# MCU.net
KiCad netlist of a schematic drawn in Altium Designer
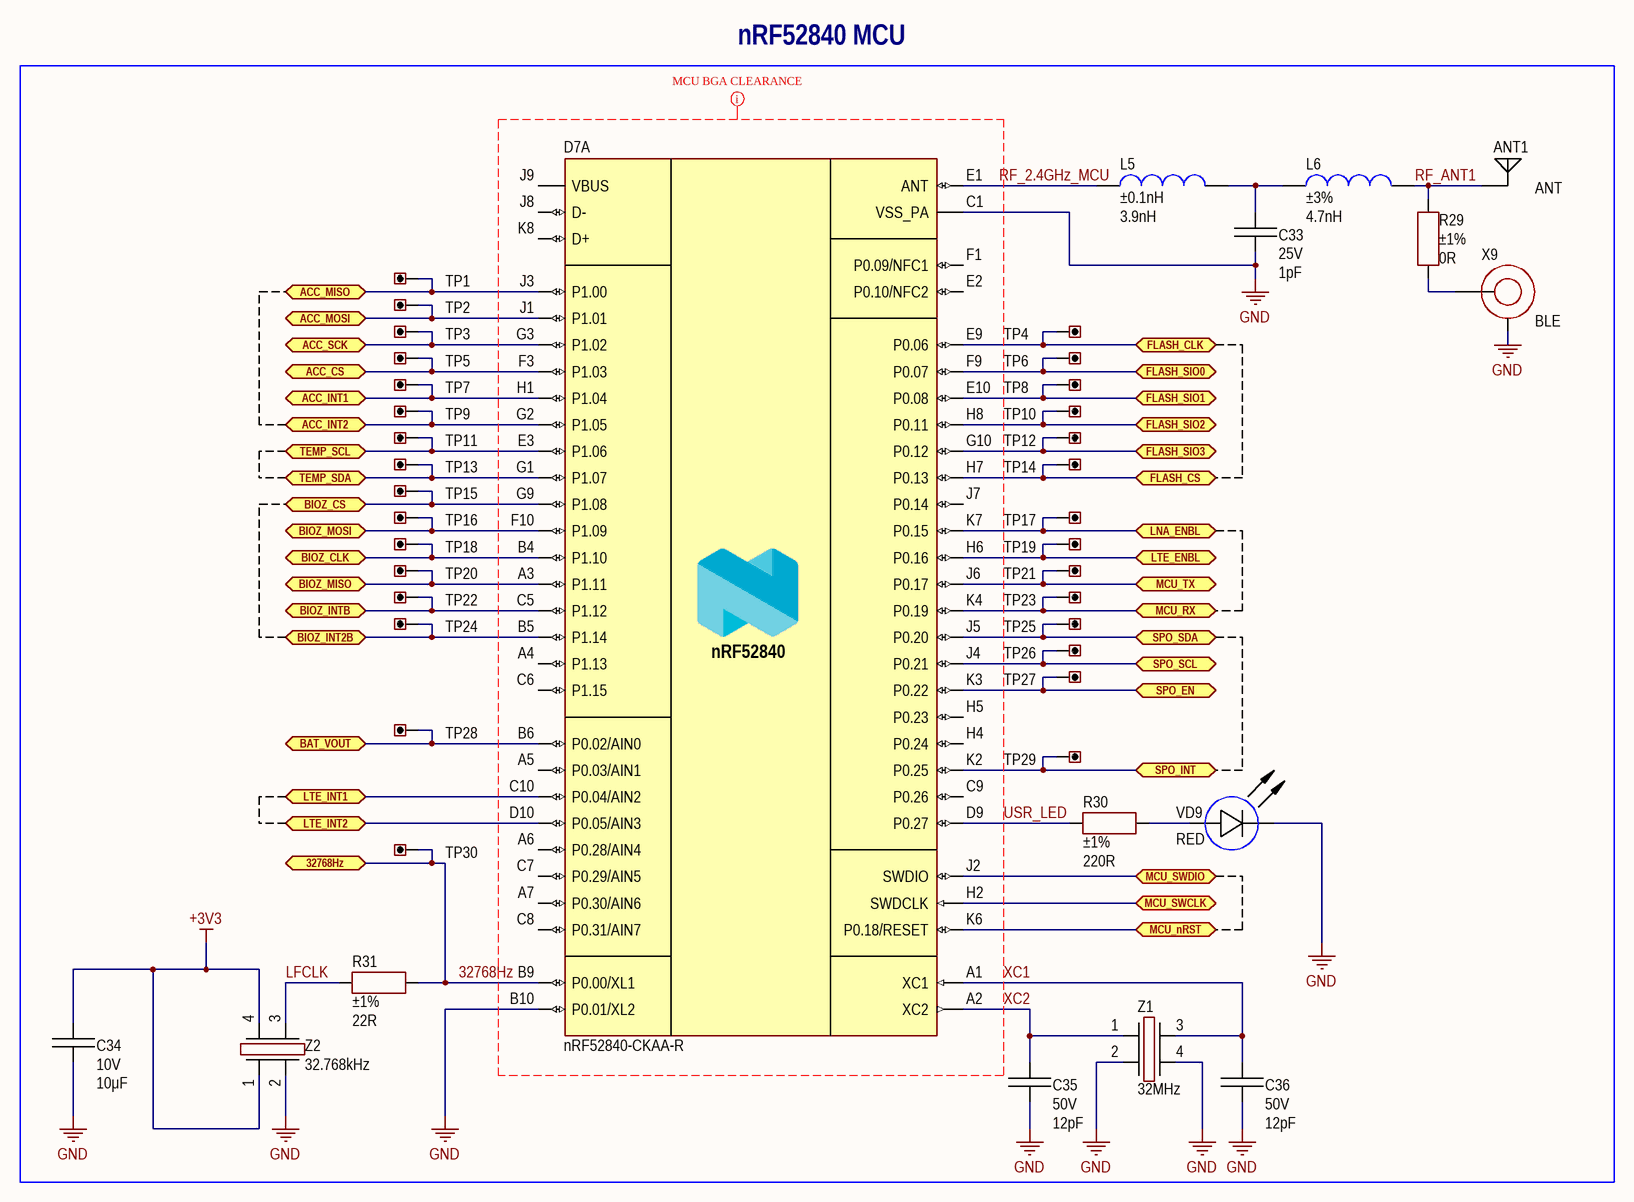
[diagram p0: MCU.SchDoc]

(export (version "E")
  (design (tool "Eeschema 10.0.6"))
  (components
    (comp (ref "ANT1")
      (value "~")
      (footprint "ANT: ANT2012LL00R2400A")
      (description "2.45GHz Bluetooth, ISM, Wi-Fi, Zigbee Chip RF Antenna 2.4GHz ~ 2.5GHz 3.77dBi Solder Surface Mount")
      (fields
        (field (name "MANUFACTURER") "Yageo")
        (field (name "VALUEMANUFACTURERPARTNUMBER") "Ceramic antenna, 2x1.25mm")
        (field (name "COMMENTTEXT") "ANT")
      )
      (libsource (lib "MyLib") (part "ANT2012LL00R2400A"))
    )
    (comp (ref "C33")
      (value "1pF")
      (footprint "CAP: 0201")
      (description "1 pF ±0.05pF 25V Ceramic Capacitor C0G, NP0 0201 (0603 Metric)")
      (fields
        (field (name "MANUFACTURER") "Murata Electronics")
        (field (name "PARTNUMBER") "GJM0335C1E1R0WB01D")
        (field (name "VOLTAGE") "25V")
      )
      (libsource (lib "capacitor") (part "Ceramic_0201"))
    )
    (comp (ref "C34")
      (value "10μF")
      (footprint "CAP: 0805")
      (description "10 µF ±10% 10V Ceramic Capacitor X7R 0805 (2012 Metric)")
      (fields
        (field (name "MANUFACTURER") "Yageo")
        (field (name "PARTNUMBER") "CC0805KFX7R6BB106")
        (field (name "VOLTAGE") "10V")
      )
      (libsource (lib "capacitor") (part "Ceramic_0805"))
    )
    (comp (ref "C35")
      (value "12pF")
      (footprint "CAP: 0805")
      (description "12 pF ±1% 50V Ceramic Capacitor C0G, NP0 0805 (2012 Metric)")
      (fields
        (field (name "MANUFACTURER") "Yageo")
        (field (name "PARTNUMBER") "CC0805FRNPO9BN120")
        (field (name "VOLTAGE") "50V")
      )
      (libsource (lib "capacitor") (part "Ceramic_0805"))
    )
    (comp (ref "C36")
      (value "12pF")
      (footprint "CAP: 0805")
      (description "12 pF ±1% 50V Ceramic Capacitor C0G, NP0 0805 (2012 Metric)")
      (fields
        (field (name "MANUFACTURER") "Yageo")
        (field (name "PARTNUMBER") "CC0805FRNPO9BN120")
        (field (name "VOLTAGE") "50V")
      )
      (libsource (lib "capacitor") (part "Ceramic_0805"))
    )
    (comp (ref "D7")
      (value "~")
      (footprint "MCU: nRF52840_WLCP93")
      (description "MCU")
      (fields
        (field (name "MANUFACTURER") "Nordic Semiconductor")
        (field (name "VALUEMANUFACTURERPARTNUMBER") "IC microcontroller, 32bit, Cortex-M4, 64 MHz, 1 MB, 256 kB, , , 93-WLCSP")
        (field (name "PARTNUMBER") "nRF52840-CKAA-R")
      )
      (libsource (lib "MyLib") (part "nRF52840"))
    )
    (comp (ref "L5")
      (value "3.9nH")
      (footprint "IND: 0201")
      (description "3.9 nH Unshielded Thick Film Inductor 400 mA 300mOhm Max 0201 (0603 Metric)")
      (fields
        (field (name "MANUFACTURER") "Murata Electronics")
        (field (name "PARTNUMBER") "LQP03TN3N9B02D")
        (field (name "TOLERANCE") "±0.1nH")
      )
      (libsource (lib "inductor") (part "Inductor_0201"))
    )
    (comp (ref "L6")
      (value "4.7nH")
      (footprint "IND: 0201")
      (description "4.7 nH Unshielded Thick Film Inductor 350 mA 400mOhm Max 0201 (0603 Metric)")
      (fields
        (field (name "MANUFACTURER") "Murata Electronics")
        (field (name "PARTNUMBER") "LQP03TN4N7H02D")
        (field (name "TOLERANCE") "±3%")
      )
      (libsource (lib "inductor") (part "Inductor_0201"))
    )
    (comp (ref "R29")
      (value "0R")
      (footprint "RES: 0201")
      (description "0 Ohms Jumper 0.05W, 1/20W Chip Resistor 0201 (0603 Metric) Moisture Resistant Thick Film")
      (fields
        (field (name "MANUFACTURER") "Yageo")
        (field (name "PARTNUMBER") "RC0201FR-070RL")
        (field (name "TOLERANCE") "±1%")
      )
      (libsource (lib "resistor") (part "Resistor_0201"))
    )
    (comp (ref "R30")
      (value "220R")
      (footprint "RES: 0805")
      (description "22 Ohms ±1% 0.125W, 1/8W Chip Resistor 0805 (2012 Metric) Moisture Resistant Thick Film")
      (fields
        (field (name "MANUFACTURER") "Yageo")
        (field (name "PARTNUMBER") "RC0805JR-07220RL")
        (field (name "TOLERANCE") "±1%")
      )
      (libsource (lib "resistor") (part "Resistor_0805"))
    )
    (comp (ref "R31")
      (value "22R")
      (footprint "RES: 0805")
      (description "22 Ohms ±1% 0.125W, 1/8W Chip Resistor 0805 (2012 Metric) Moisture Resistant Thick Film")
      (fields
        (field (name "MANUFACTURER") "Yageo")
        (field (name "PARTNUMBER") "RC0805FR-0722RL")
        (field (name "TOLERANCE") "±1%")
      )
      (libsource (lib "resistor") (part "Resistor_0805"))
    )
    (comp (ref "TP1")
      (value "~")
      (footprint "CON: 5000 (Keystone)")
      (fields
        (field (name "MANUFACTURER") "Keystone")
        (field (name "VALUEMANUFACTURERPARTNUMBER") "Test point, Keystone, 5000")
        (field (name "PARTNUMBER") "5000")
      )
      (libsource (lib "connector") (part "Connector_Test_Point"))
    )
    (comp (ref "TP2")
      (value "~")
      (footprint "CON: 5000 (Keystone)")
      (fields
        (field (name "MANUFACTURER") "Keystone")
        (field (name "VALUEMANUFACTURERPARTNUMBER") "Test point, Keystone, 5000")
        (field (name "PARTNUMBER") "5000")
      )
      (libsource (lib "connector") (part "Connector_Test_Point"))
    )
    (comp (ref "TP3")
      (value "~")
      (footprint "CON: 5000 (Keystone)")
      (fields
        (field (name "MANUFACTURER") "Keystone")
        (field (name "VALUEMANUFACTURERPARTNUMBER") "Test point, Keystone, 5000")
        (field (name "PARTNUMBER") "5000")
      )
      (libsource (lib "connector") (part "Connector_Test_Point"))
    )
    (comp (ref "TP4")
      (value "~")
      (footprint "CON: 5000 (Keystone)")
      (fields
        (field (name "MANUFACTURER") "Keystone")
        (field (name "VALUEMANUFACTURERPARTNUMBER") "Test point, Keystone, 5000")
        (field (name "PARTNUMBER") "5000")
      )
      (libsource (lib "") (part "Connector_Test_Point_1"))
    )
    (comp (ref "TP5")
      (value "~")
      (footprint "CON: 5000 (Keystone)")
      (fields
        (field (name "MANUFACTURER") "Keystone")
        (field (name "VALUEMANUFACTURERPARTNUMBER") "Test point, Keystone, 5000")
        (field (name "PARTNUMBER") "5000")
      )
      (libsource (lib "connector") (part "Connector_Test_Point"))
    )
    (comp (ref "TP6")
      (value "~")
      (footprint "CON: 5000 (Keystone)")
      (fields
        (field (name "MANUFACTURER") "Keystone")
        (field (name "VALUEMANUFACTURERPARTNUMBER") "Test point, Keystone, 5000")
        (field (name "PARTNUMBER") "5000")
      )
      (libsource (lib "") (part "Connector_Test_Point_1"))
    )
    (comp (ref "TP7")
      (value "~")
      (footprint "CON: 5000 (Keystone)")
      (fields
        (field (name "MANUFACTURER") "Keystone")
        (field (name "VALUEMANUFACTURERPARTNUMBER") "Test point, Keystone, 5000")
        (field (name "PARTNUMBER") "5000")
      )
      (libsource (lib "connector") (part "Connector_Test_Point"))
    )
    (comp (ref "TP8")
      (value "~")
      (footprint "CON: 5000 (Keystone)")
      (fields
        (field (name "MANUFACTURER") "Keystone")
        (field (name "VALUEMANUFACTURERPARTNUMBER") "Test point, Keystone, 5000")
        (field (name "PARTNUMBER") "5000")
      )
      (libsource (lib "") (part "Connector_Test_Point_1"))
    )
    (comp (ref "TP9")
      (value "~")
      (footprint "CON: 5000 (Keystone)")
      (fields
        (field (name "MANUFACTURER") "Keystone")
        (field (name "VALUEMANUFACTURERPARTNUMBER") "Test point, Keystone, 5000")
        (field (name "PARTNUMBER") "5000")
      )
      (libsource (lib "connector") (part "Connector_Test_Point"))
    )
    (comp (ref "TP10")
      (value "~")
      (footprint "CON: 5000 (Keystone)")
      (fields
        (field (name "MANUFACTURER") "Keystone")
        (field (name "VALUEMANUFACTURERPARTNUMBER") "Test point, Keystone, 5000")
        (field (name "PARTNUMBER") "5000")
      )
      (libsource (lib "") (part "Connector_Test_Point_1"))
    )
    (comp (ref "TP11")
      (value "~")
      (footprint "CON: 5000 (Keystone)")
      (fields
        (field (name "MANUFACTURER") "Keystone")
        (field (name "VALUEMANUFACTURERPARTNUMBER") "Test point, Keystone, 5000")
        (field (name "PARTNUMBER") "5000")
      )
      (libsource (lib "connector") (part "Connector_Test_Point"))
    )
    (comp (ref "TP12")
      (value "~")
      (footprint "CON: 5000 (Keystone)")
      (fields
        (field (name "MANUFACTURER") "Keystone")
        (field (name "VALUEMANUFACTURERPARTNUMBER") "Test point, Keystone, 5000")
        (field (name "PARTNUMBER") "5000")
      )
      (libsource (lib "") (part "Connector_Test_Point_1"))
    )
    (comp (ref "TP13")
      (value "~")
      (footprint "CON: 5000 (Keystone)")
      (fields
        (field (name "MANUFACTURER") "Keystone")
        (field (name "VALUEMANUFACTURERPARTNUMBER") "Test point, Keystone, 5000")
        (field (name "PARTNUMBER") "5000")
      )
      (libsource (lib "connector") (part "Connector_Test_Point"))
    )
    (comp (ref "TP14")
      (value "~")
      (footprint "CON: 5000 (Keystone)")
      (fields
        (field (name "MANUFACTURER") "Keystone")
        (field (name "VALUEMANUFACTURERPARTNUMBER") "Test point, Keystone, 5000")
        (field (name "PARTNUMBER") "5000")
      )
      (libsource (lib "") (part "Connector_Test_Point_1"))
    )
    (comp (ref "TP15")
      (value "~")
      (footprint "CON: 5000 (Keystone)")
      (fields
        (field (name "MANUFACTURER") "Keystone")
        (field (name "VALUEMANUFACTURERPARTNUMBER") "Test point, Keystone, 5000")
        (field (name "PARTNUMBER") "5000")
      )
      (libsource (lib "connector") (part "Connector_Test_Point"))
    )
    (comp (ref "TP16")
      (value "~")
      (footprint "CON: 5000 (Keystone)")
      (fields
        (field (name "MANUFACTURER") "Keystone")
        (field (name "VALUEMANUFACTURERPARTNUMBER") "Test point, Keystone, 5000")
        (field (name "PARTNUMBER") "5000")
      )
      (libsource (lib "connector") (part "Connector_Test_Point"))
    )
    (comp (ref "TP17")
      (value "~")
      (footprint "CON: 5000 (Keystone)")
      (fields
        (field (name "MANUFACTURER") "Keystone")
        (field (name "VALUEMANUFACTURERPARTNUMBER") "Test point, Keystone, 5000")
        (field (name "PARTNUMBER") "5000")
      )
      (libsource (lib "") (part "Connector_Test_Point_1"))
    )
    (comp (ref "TP18")
      (value "~")
      (footprint "CON: 5000 (Keystone)")
      (fields
        (field (name "MANUFACTURER") "Keystone")
        (field (name "VALUEMANUFACTURERPARTNUMBER") "Test point, Keystone, 5000")
        (field (name "PARTNUMBER") "5000")
      )
      (libsource (lib "connector") (part "Connector_Test_Point"))
    )
    (comp (ref "TP19")
      (value "~")
      (footprint "CON: 5000 (Keystone)")
      (fields
        (field (name "MANUFACTURER") "Keystone")
        (field (name "VALUEMANUFACTURERPARTNUMBER") "Test point, Keystone, 5000")
        (field (name "PARTNUMBER") "5000")
      )
      (libsource (lib "") (part "Connector_Test_Point_1"))
    )
    (comp (ref "TP20")
      (value "~")
      (footprint "CON: 5000 (Keystone)")
      (fields
        (field (name "MANUFACTURER") "Keystone")
        (field (name "VALUEMANUFACTURERPARTNUMBER") "Test point, Keystone, 5000")
        (field (name "PARTNUMBER") "5000")
      )
      (libsource (lib "connector") (part "Connector_Test_Point"))
    )
    (comp (ref "TP21")
      (value "~")
      (footprint "CON: 5000 (Keystone)")
      (fields
        (field (name "MANUFACTURER") "Keystone")
        (field (name "VALUEMANUFACTURERPARTNUMBER") "Test point, Keystone, 5000")
        (field (name "PARTNUMBER") "5000")
      )
      (libsource (lib "") (part "Connector_Test_Point_1"))
    )
    (comp (ref "TP22")
      (value "~")
      (footprint "CON: 5000 (Keystone)")
      (fields
        (field (name "MANUFACTURER") "Keystone")
        (field (name "VALUEMANUFACTURERPARTNUMBER") "Test point, Keystone, 5000")
        (field (name "PARTNUMBER") "5000")
      )
      (libsource (lib "connector") (part "Connector_Test_Point"))
    )
    (comp (ref "TP23")
      (value "~")
      (footprint "CON: 5000 (Keystone)")
      (fields
        (field (name "MANUFACTURER") "Keystone")
        (field (name "VALUEMANUFACTURERPARTNUMBER") "Test point, Keystone, 5000")
        (field (name "PARTNUMBER") "5000")
      )
      (libsource (lib "") (part "Connector_Test_Point_1"))
    )
    (comp (ref "TP24")
      (value "~")
      (footprint "CON: 5000 (Keystone)")
      (fields
        (field (name "MANUFACTURER") "Keystone")
        (field (name "VALUEMANUFACTURERPARTNUMBER") "Test point, Keystone, 5000")
        (field (name "PARTNUMBER") "5000")
      )
      (libsource (lib "connector") (part "Connector_Test_Point"))
    )
    (comp (ref "TP25")
      (value "~")
      (footprint "CON: 5000 (Keystone)")
      (fields
        (field (name "MANUFACTURER") "Keystone")
        (field (name "VALUEMANUFACTURERPARTNUMBER") "Test point, Keystone, 5000")
        (field (name "PARTNUMBER") "5000")
      )
      (libsource (lib "") (part "Connector_Test_Point_1"))
    )
    (comp (ref "TP26")
      (value "~")
      (footprint "CON: 5000 (Keystone)")
      (fields
        (field (name "MANUFACTURER") "Keystone")
        (field (name "VALUEMANUFACTURERPARTNUMBER") "Test point, Keystone, 5000")
        (field (name "PARTNUMBER") "5000")
      )
      (libsource (lib "") (part "Connector_Test_Point_1"))
    )
    (comp (ref "TP27")
      (value "~")
      (footprint "CON: 5000 (Keystone)")
      (fields
        (field (name "MANUFACTURER") "Keystone")
        (field (name "VALUEMANUFACTURERPARTNUMBER") "Test point, Keystone, 5000")
        (field (name "PARTNUMBER") "5000")
      )
      (libsource (lib "") (part "Connector_Test_Point_1"))
    )
    (comp (ref "TP28")
      (value "~")
      (footprint "CON: 5000 (Keystone)")
      (fields
        (field (name "MANUFACTURER") "Keystone")
        (field (name "VALUEMANUFACTURERPARTNUMBER") "Test point, Keystone, 5000")
        (field (name "PARTNUMBER") "5000")
      )
      (libsource (lib "connector") (part "Connector_Test_Point"))
    )
    (comp (ref "TP29")
      (value "~")
      (footprint "CON: 5000 (Keystone)")
      (fields
        (field (name "MANUFACTURER") "Keystone")
        (field (name "VALUEMANUFACTURERPARTNUMBER") "Test point, Keystone, 5000")
        (field (name "PARTNUMBER") "5000")
      )
      (libsource (lib "") (part "Connector_Test_Point_1"))
    )
    (comp (ref "TP30")
      (value "~")
      (footprint "CON: 5000 (Keystone)")
      (fields
        (field (name "MANUFACTURER") "Keystone")
        (field (name "VALUEMANUFACTURERPARTNUMBER") "Test point, Keystone, 5000")
        (field (name "PARTNUMBER") "5000")
      )
      (libsource (lib "connector") (part "Connector_Test_Point"))
    )
    (comp (ref "VD9")
      (value "~")
      (footprint "LED: 0805R")
      (description "Red 625nm LED Indication - Discrete 1.8V 0805 (2012 Metric)")
      (fields
        (field (name "MANUFACTURER") "Kingbright")
        (field (name "VALUEMANUFACTURERPARTNUMBER") "LED, RED, 30mA, 1.8V, 0805, -55...+150°C")
        (field (name "COLOR") "RED")
      )
      (libsource (lib "diode") (part "LED_single"))
    )
    (comp (ref "X9")
      (value "~")
      (footprint "CON: u.Fl")
      (description "U.FL (UMCC) Connector Receptacle, Male Pin 50Ohm Surface Mount Solder")
      (fields
        (field (name "MANUFACTURER") "Hirose Electric")
        (field (name "VALUEMANUFACTURERPARTNUMBER") "Connector u.FL, 50 Ohm, 6GHz")
        (field (name "COMMENTTEXT") "BLE")
      )
      (libsource (lib "connector") (part "Connector_uFL"))
    )
    (comp (ref "Z1")
      (value "~")
      (footprint "OSC: 2016")
      (description "32 MHz ±10ppm Crystal 8pF 60 Ohms 4-SMD, No Lead")
      (fields
        (field (name "MANUFACTURER") "EPSON")
        (field (name "PARTNUMBER") "FA-128 32.0000MF10Z-AJ3")
        (field (name "FREQUENCY") "32MHz")
      )
      (libsource (lib "oscilator") (part "Crystal_2016"))
    )
    (comp (ref "Z2")
      (value "~")
      (footprint "OSC: 5032G")
      (description "32.768 kHz XO (Standard) LVCMOS Oscillator 1.8V Enable/Disable 4-SMD, No Lead")
      (fields
        (field (name "MANUFACTURER") "Abracon LLC")
        (field (name "PARTNUMBER") "KD3270037")
        (field (name "FREQUENCY") "32.768kHz")
      )
      (libsource (lib "oscilator") (part "Oscilator_5032"))
    )
  )
  (nets
    (net (code "1") (name "+3V3") (class "Default")
      (node (ref "C34") (pin "2") (pinfunction "2_2") (pintype "passive"))
      (node (ref "Z2") (pin "1") (pinfunction "1_1") (pintype "passive"))
      (node (ref "Z2") (pin "4") (pinfunction "4_4") (pintype "passive"))
    )
    (net (code "2") (name "/32768Hz") (class "Default")
      (node (ref "D7") (pin "B9") (pinfunction "P0.00/XL1_B9") (pintype "bidirectional"))
      (node (ref "R31") (pin "1") (pinfunction "1_1") (pintype "passive"))
      (node (ref "TP30") (pin "1") (pinfunction "1_1") (pintype "passive"))
    )
    (net (code "3") (name "/ACC_CS") (class "Default")
      (node (ref "D7") (pin "F3") (pinfunction "P1.03_F3") (pintype "bidirectional"))
      (node (ref "TP5") (pin "1") (pinfunction "1_1") (pintype "passive"))
    )
    (net (code "4") (name "/ACC_INT1") (class "Default")
      (node (ref "D7") (pin "H1") (pinfunction "P1.04_H1") (pintype "bidirectional"))
      (node (ref "TP7") (pin "1") (pinfunction "1_1") (pintype "passive"))
    )
    (net (code "5") (name "/ACC_INT2") (class "Default")
      (node (ref "D7") (pin "G2") (pinfunction "P1.05_G2") (pintype "bidirectional"))
      (node (ref "TP9") (pin "1") (pinfunction "1_1") (pintype "passive"))
    )
    (net (code "6") (name "/ACC_MISO") (class "Default")
      (node (ref "D7") (pin "J3") (pinfunction "P1.00_J3") (pintype "bidirectional"))
      (node (ref "TP1") (pin "1") (pinfunction "1_1") (pintype "passive"))
    )
    (net (code "7") (name "/ACC_MOSI") (class "Default")
      (node (ref "D7") (pin "J1") (pinfunction "P1.01_J1") (pintype "bidirectional"))
      (node (ref "TP2") (pin "1") (pinfunction "1_1") (pintype "passive"))
    )
    (net (code "8") (name "/ACC_SCK") (class "Default")
      (node (ref "D7") (pin "G3") (pinfunction "P1.02_G3") (pintype "bidirectional"))
      (node (ref "TP3") (pin "1") (pinfunction "1_1") (pintype "passive"))
    )
    (net (code "9") (name "/BAT_VOUT") (class "Default")
      (node (ref "D7") (pin "B6") (pinfunction "P0.02/AIN0_B6") (pintype "bidirectional"))
      (node (ref "TP28") (pin "1") (pinfunction "1_1") (pintype "passive"))
    )
    (net (code "10") (name "/BIOZ_CLK") (class "Default")
      (node (ref "D7") (pin "B4") (pinfunction "P1.10_B4") (pintype "bidirectional"))
      (node (ref "TP18") (pin "1") (pinfunction "1_1") (pintype "passive"))
    )
    (net (code "11") (name "/BIOZ_CS") (class "Default")
      (node (ref "D7") (pin "G9") (pinfunction "P1.08_G9") (pintype "bidirectional"))
      (node (ref "TP15") (pin "1") (pinfunction "1_1") (pintype "passive"))
    )
    (net (code "12") (name "/BIOZ_INT2B") (class "Default")
      (node (ref "D7") (pin "B5") (pinfunction "P1.14_B5") (pintype "bidirectional"))
      (node (ref "TP24") (pin "1") (pinfunction "1_1") (pintype "passive"))
    )
    (net (code "13") (name "/BIOZ_INTB") (class "Default")
      (node (ref "D7") (pin "C5") (pinfunction "P1.12_C5") (pintype "bidirectional"))
      (node (ref "TP22") (pin "1") (pinfunction "1_1") (pintype "passive"))
    )
    (net (code "14") (name "/BIOZ_MISO") (class "Default")
      (node (ref "D7") (pin "A3") (pinfunction "P1.11_A3") (pintype "bidirectional"))
      (node (ref "TP20") (pin "1") (pinfunction "1_1") (pintype "passive"))
    )
    (net (code "15") (name "/BIOZ_MOSI") (class "Default")
      (node (ref "D7") (pin "F10") (pinfunction "P1.09_F10") (pintype "bidirectional"))
      (node (ref "TP16") (pin "1") (pinfunction "1_1") (pintype "passive"))
    )
    (net (code "16") (name "/FLASH_CLK") (class "Default")
      (node (ref "D7") (pin "E9") (pinfunction "P0.06_E9") (pintype "bidirectional"))
      (node (ref "TP4") (pin "1") (pinfunction "1_1") (pintype "passive"))
    )
    (net (code "17") (name "/FLASH_CS") (class "Default")
      (node (ref "D7") (pin "H7") (pinfunction "P0.13_H7") (pintype "bidirectional"))
      (node (ref "TP14") (pin "1") (pinfunction "1_1") (pintype "passive"))
    )
    (net (code "18") (name "/FLASH_SIO0") (class "Default")
      (node (ref "D7") (pin "F9") (pinfunction "P0.07_F9") (pintype "bidirectional"))
      (node (ref "TP6") (pin "1") (pinfunction "1_1") (pintype "passive"))
    )
    (net (code "19") (name "/FLASH_SIO1") (class "Default")
      (node (ref "D7") (pin "E10") (pinfunction "P0.08_E10") (pintype "bidirectional"))
      (node (ref "TP8") (pin "1") (pinfunction "1_1") (pintype "passive"))
    )
    (net (code "20") (name "/FLASH_SIO2") (class "Default")
      (node (ref "D7") (pin "H8") (pinfunction "P0.11_H8") (pintype "bidirectional"))
      (node (ref "TP10") (pin "1") (pinfunction "1_1") (pintype "passive"))
    )
    (net (code "21") (name "/FLASH_SIO3") (class "Default")
      (node (ref "D7") (pin "G10") (pinfunction "P0.12_G10") (pintype "bidirectional"))
      (node (ref "TP12") (pin "1") (pinfunction "1_1") (pintype "passive"))
    )
    (net (code "22") (name "/LFCLK") (class "Default")
      (node (ref "R31") (pin "2") (pinfunction "2_2") (pintype "passive"))
      (node (ref "Z2") (pin "3") (pinfunction "3_3") (pintype "passive"))
    )
    (net (code "23") (name "/LNA_ENBL") (class "Default")
      (node (ref "D7") (pin "K7") (pinfunction "P0.15_K7") (pintype "bidirectional"))
      (node (ref "TP17") (pin "1") (pinfunction "1_1") (pintype "passive"))
    )
    (net (code "24") (name "/LTE_ENBL") (class "Default")
      (node (ref "D7") (pin "H6") (pinfunction "P0.16_H6") (pintype "bidirectional"))
      (node (ref "TP19") (pin "1") (pinfunction "1_1") (pintype "passive"))
    )
    (net (code "25") (name "/LTE_INT1") (class "Default")
      (node (ref "D7") (pin "C10") (pinfunction "P0.04/AIN2_C10") (pintype "bidirectional"))
    )
    (net (code "26") (name "/LTE_INT2") (class "Default")
      (node (ref "D7") (pin "D10") (pinfunction "P0.05/AIN3_D10") (pintype "bidirectional"))
    )
    (net (code "27") (name "/MCU_RX") (class "Default")
      (node (ref "D7") (pin "K4") (pinfunction "P0.19_K4") (pintype "bidirectional"))
      (node (ref "TP23") (pin "1") (pinfunction "1_1") (pintype "passive"))
    )
    (net (code "28") (name "/MCU_SWCLK") (class "Default")
      (node (ref "D7") (pin "H2") (pinfunction "SWDCLK_H2") (pintype "input"))
    )
    (net (code "29") (name "/MCU_SWDIO") (class "Default")
      (node (ref "D7") (pin "J2") (pinfunction "SWDIO_J2") (pintype "bidirectional"))
    )
    (net (code "30") (name "/MCU_TX") (class "Default")
      (node (ref "D7") (pin "J6") (pinfunction "P0.17_J6") (pintype "bidirectional"))
      (node (ref "TP21") (pin "1") (pinfunction "1_1") (pintype "passive"))
    )
    (net (code "31") (name "/MCU_nRST") (class "Default")
      (node (ref "D7") (pin "K6") (pinfunction "P0.18/RESET_K6") (pintype "bidirectional"))
    )
    (net (code "32") (name "/RF_2.4GHz_MCU") (class "Default")
      (node (ref "D7") (pin "E1") (pinfunction "ANT_E1") (pintype "bidirectional"))
      (node (ref "L5") (pin "2") (pinfunction "2_2") (pintype "passive"))
    )
    (net (code "33") (name "/RF_ANT1") (class "Default")
      (node (ref "ANT1") (pin "1") (pinfunction "1_1") (pintype "passive"))
      (node (ref "L6") (pin "1") (pinfunction "1_1") (pintype "passive"))
      (node (ref "R29") (pin "2") (pinfunction "2_2") (pintype "passive"))
    )
    (net (code "34") (name "/SPO_EN") (class "Default")
      (node (ref "D7") (pin "K3") (pinfunction "P0.22_K3") (pintype "bidirectional"))
      (node (ref "TP27") (pin "1") (pinfunction "1_1") (pintype "passive"))
    )
    (net (code "35") (name "/SPO_INT") (class "Default")
      (node (ref "D7") (pin "K2") (pinfunction "P0.25_K2") (pintype "bidirectional"))
      (node (ref "TP29") (pin "1") (pinfunction "1_1") (pintype "passive"))
    )
    (net (code "36") (name "/SPO_SCL") (class "Default")
      (node (ref "D7") (pin "J4") (pinfunction "P0.21_J4") (pintype "bidirectional"))
      (node (ref "TP26") (pin "1") (pinfunction "1_1") (pintype "passive"))
    )
    (net (code "37") (name "/SPO_SDA") (class "Default")
      (node (ref "D7") (pin "J5") (pinfunction "P0.20_J5") (pintype "bidirectional"))
      (node (ref "TP25") (pin "1") (pinfunction "1_1") (pintype "passive"))
    )
    (net (code "38") (name "/TEMP_SCL") (class "Default")
      (node (ref "D7") (pin "E3") (pinfunction "P1.06_E3") (pintype "bidirectional"))
      (node (ref "TP11") (pin "1") (pinfunction "1_1") (pintype "passive"))
    )
    (net (code "39") (name "/TEMP_SDA") (class "Default")
      (node (ref "D7") (pin "G1") (pinfunction "P1.07_G1") (pintype "bidirectional"))
      (node (ref "TP13") (pin "1") (pinfunction "1_1") (pintype "passive"))
    )
    (net (code "40") (name "/USR_LED") (class "Default")
      (node (ref "D7") (pin "D9") (pinfunction "P0.27_D9") (pintype "bidirectional"))
      (node (ref "R30") (pin "2") (pinfunction "2_2") (pintype "passive"))
    )
    (net (code "41") (name "/XC1") (class "Default")
      (node (ref "C36") (pin "2") (pinfunction "2_2") (pintype "passive"))
      (node (ref "D7") (pin "A1") (pinfunction "XC1_A1") (pintype "input"))
      (node (ref "Z1") (pin "3") (pinfunction "3_3") (pintype "passive"))
    )
    (net (code "42") (name "/XC2") (class "Default")
      (node (ref "C35") (pin "2") (pinfunction "2_2") (pintype "passive"))
      (node (ref "D7") (pin "A2") (pinfunction "XC2_A2") (pintype "output"))
      (node (ref "Z1") (pin "1") (pinfunction "1_1") (pintype "passive"))
    )
    (net (code "43") (name "GND") (class "Default")
      (node (ref "C33") (pin "1") (pinfunction "1_1") (pintype "passive"))
      (node (ref "C34") (pin "1") (pinfunction "1_1") (pintype "passive"))
      (node (ref "C35") (pin "1") (pinfunction "1_1") (pintype "passive"))
      (node (ref "C36") (pin "1") (pinfunction "1_1") (pintype "passive"))
      (node (ref "D7") (pin "B10") (pinfunction "P0.01/XL2_B10") (pintype "bidirectional"))
      (node (ref "D7") (pin "C1") (pinfunction "VSS_PA_C1") (pintype "power_in"))
      (node (ref "VD9") (pin "2") (pinfunction "C_2") (pintype "passive"))
      (node (ref "X9") (pin "2") (pinfunction "2_2") (pintype "passive"))
      (node (ref "Z1") (pin "2") (pinfunction "2_2") (pintype "passive"))
      (node (ref "Z1") (pin "4") (pinfunction "4_4") (pintype "passive"))
      (node (ref "Z2") (pin "2") (pinfunction "2_2") (pintype "passive"))
    )
    (net (code "44") (name "Net-(C33-Pad2)") (class "Default")
      (node (ref "C33") (pin "2") (pinfunction "2_2") (pintype "passive"))
      (node (ref "L5") (pin "1") (pinfunction "1_1") (pintype "passive"))
      (node (ref "L6") (pin "2") (pinfunction "2_2") (pintype "passive"))
    )
    (net (code "45") (name "Net-(R29-Pad1)") (class "Default")
      (node (ref "R29") (pin "1") (pinfunction "1_1") (pintype "passive"))
      (node (ref "X9") (pin "1") (pinfunction "1_1") (pintype "passive"))
    )
    (net (code "46") (name "Net-(VD9-A)") (class "Default")
      (node (ref "R30") (pin "1") (pinfunction "1_1") (pintype "passive"))
      (node (ref "VD9") (pin "1") (pinfunction "A_1") (pintype "passive"))
    )
    (net (code "47") (name "unconnected-(D7A-D+-PadK8)") (class "Default")
      (node (ref "D7") (pin "K8") (pinfunction "D+_K8") (pintype "bidirectional"))
    )
    (net (code "48") (name "unconnected-(D7A-D--PadJ8)") (class "Default")
      (node (ref "D7") (pin "J8") (pinfunction "D-_J8") (pintype "bidirectional"))
    )
    (net (code "49") (name "unconnected-(D7A-P0.03{slash}AIN1-PadA5)") (class "Default")
      (node (ref "D7") (pin "A5") (pinfunction "P0.03/AIN1_A5") (pintype "bidirectional"))
    )
    (net (code "50") (name "unconnected-(D7A-P0.09{slash}NFC1-PadF1)") (class "Default")
      (node (ref "D7") (pin "F1") (pinfunction "P0.09/NFC1_F1") (pintype "bidirectional"))
    )
    (net (code "51") (name "unconnected-(D7A-P0.10{slash}NFC2-PadE2)") (class "Default")
      (node (ref "D7") (pin "E2") (pinfunction "P0.10/NFC2_E2") (pintype "bidirectional"))
    )
    (net (code "52") (name "unconnected-(D7A-P0.14-PadJ7)") (class "Default")
      (node (ref "D7") (pin "J7") (pinfunction "P0.14_J7") (pintype "bidirectional"))
    )
    (net (code "53") (name "unconnected-(D7A-P0.23-PadH5)") (class "Default")
      (node (ref "D7") (pin "H5") (pinfunction "P0.23_H5") (pintype "bidirectional"))
    )
    (net (code "54") (name "unconnected-(D7A-P0.24-PadH4)") (class "Default")
      (node (ref "D7") (pin "H4") (pinfunction "P0.24_H4") (pintype "bidirectional"))
    )
    (net (code "55") (name "unconnected-(D7A-P0.26-PadC9)") (class "Default")
      (node (ref "D7") (pin "C9") (pinfunction "P0.26_C9") (pintype "bidirectional"))
    )
    (net (code "56") (name "unconnected-(D7A-P0.28{slash}AIN4-PadA6)") (class "Default")
      (node (ref "D7") (pin "A6") (pinfunction "P0.28/AIN4_A6") (pintype "bidirectional"))
    )
    (net (code "57") (name "unconnected-(D7A-P0.29{slash}AIN5-PadC7)") (class "Default")
      (node (ref "D7") (pin "C7") (pinfunction "P0.29/AIN5_C7") (pintype "bidirectional"))
    )
    (net (code "58") (name "unconnected-(D7A-P0.30{slash}AIN6-PadA7)") (class "Default")
      (node (ref "D7") (pin "A7") (pinfunction "P0.30/AIN6_A7") (pintype "bidirectional"))
    )
    (net (code "59") (name "unconnected-(D7A-P0.31{slash}AIN7-PadC8)") (class "Default")
      (node (ref "D7") (pin "C8") (pinfunction "P0.31/AIN7_C8") (pintype "bidirectional"))
    )
    (net (code "60") (name "unconnected-(D7A-P1.13-PadA4)") (class "Default")
      (node (ref "D7") (pin "A4") (pinfunction "P1.13_A4") (pintype "bidirectional"))
    )
    (net (code "61") (name "unconnected-(D7A-P1.15-PadC6)") (class "Default")
      (node (ref "D7") (pin "C6") (pinfunction "P1.15_C6") (pintype "bidirectional"))
    )
    (net (code "62") (name "unconnected-(D7A-VBUS-PadJ9)") (class "Default")
      (node (ref "D7") (pin "J9") (pinfunction "VBUS_J9") (pintype "power_in"))
    )
  )
)
